# Power.net
KiCad netlist of a schematic drawn in Altium Designer
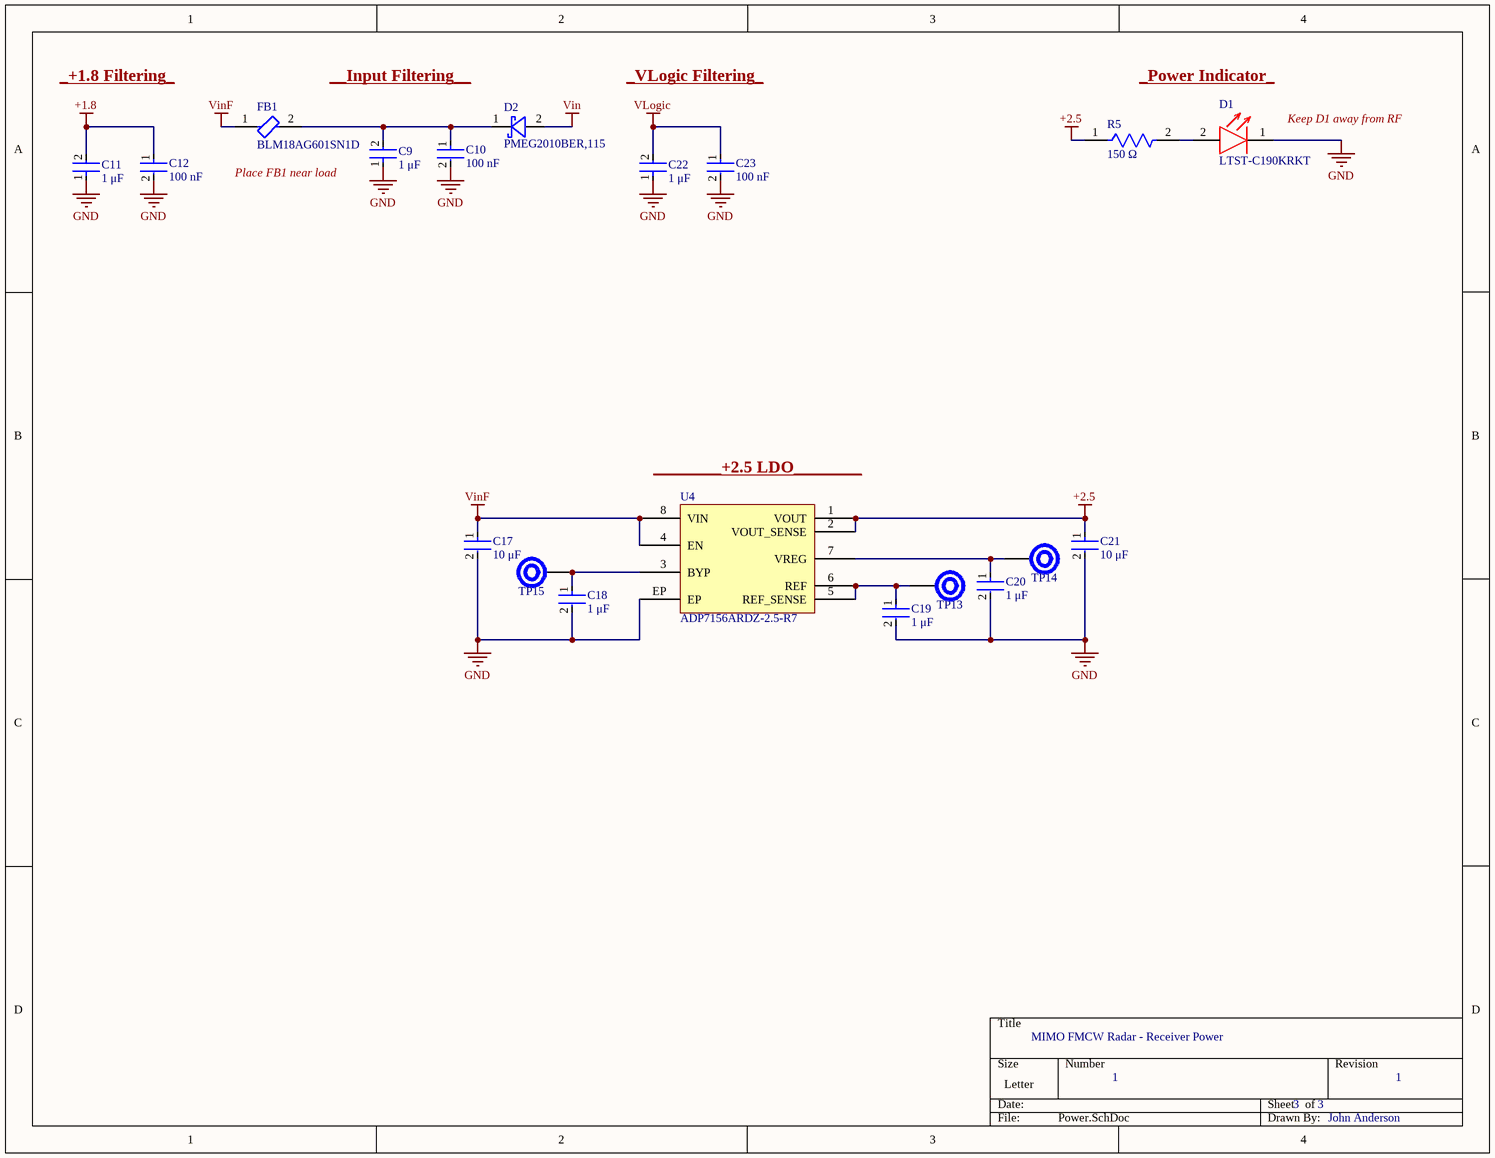
[diagram p0: Power.SchDoc]

(export (version "E")
  (design (tool "Eeschema 10.0.6"))
  (components
    (comp (ref "C9")
      (value "1 μF")
      (footprint "FP-0603-L_1_6_0_15-W_0_8-MFG")
      (libsource (lib "Power Pullers") (part "11868f565c42a9108669ba33697ecf6"))
    )
    (comp (ref "C10")
      (value "100 nF")
      (footprint "FP-CGA3E-0_3-0_1-MFG")
      (libsource (lib "Power Pullers") (part "b4654b650e69147ec39a6b967a45e02"))
    )
    (comp (ref "C11")
      (value "1 μF")
      (footprint "FP-0603-L_1_6_0_15-W_0_8-MFG")
      (libsource (lib "Power Pullers") (part "11868f565c42a9108669ba33697ecf6"))
    )
    (comp (ref "C12")
      (value "100 nF")
      (footprint "FP-CGA3E-0_3-0_1-MFG")
      (libsource (lib "Power Pullers") (part "b4654b650e69147ec39a6b967a45e02"))
    )
    (comp (ref "C17")
      (value "10 μF")
      (footprint "FP-GRM21B-0_15-IPC_C")
      (libsource (lib "Power Pullers") (part "b4654b650e69147ec39a6b967a45e02"))
    )
    (comp (ref "C18")
      (value "1 μF")
      (footprint "FP-0603-L_1_6_0_15-W_0_8-MFG")
      (libsource (lib "Power Pullers") (part "11868f565c42a9108669ba33697ecf6"))
    )
    (comp (ref "C19")
      (value "1 μF")
      (footprint "FP-0603-L_1_6_0_15-W_0_8-MFG")
      (libsource (lib "Power Pullers") (part "11868f565c42a9108669ba33697ecf6"))
    )
    (comp (ref "C20")
      (value "1 μF")
      (footprint "FP-0603-L_1_6_0_15-W_0_8-MFG")
      (libsource (lib "Power Pullers") (part "11868f565c42a9108669ba33697ecf6"))
    )
    (comp (ref "C21")
      (value "10 μF")
      (footprint "FP-GRM21B-0_15-IPC_C")
      (libsource (lib "Power Pullers") (part "b4654b650e69147ec39a6b967a45e02"))
    )
    (comp (ref "C22")
      (value "1 μF")
      (footprint "FP-0603-L_1_6_0_15-W_0_8-MFG")
      (libsource (lib "Power Pullers") (part "11868f565c42a9108669ba33697ecf6"))
    )
    (comp (ref "C23")
      (value "100 nF")
      (footprint "FP-CGA3E-0_3-0_1-MFG")
      (libsource (lib "Power Pullers") (part "b4654b650e69147ec39a6b967a45e02"))
    )
    (comp (ref "D1")
      (value "LTST-C190KRKT")
      (footprint "LTST-C190KRKT-Footprint-1")
      (description "Red, Single Color LED, Red, Water Clear")
      (libsource (lib "Power Pullers") (part "LTST-C190KRKT-Symbol-1"))
    )
    (comp (ref "D2")
      (value "PMEG2010BER,115")
      (footprint "PMEG2010BER,115-Footprint-1")
      (description "PMEG2010 Series 20 V 1 A SMT Low VF MEGA Schottky Barrier Rectifier - SOD-123W")
      (libsource (lib "Power Pullers") (part "PMEG2010BER,115-Symbol-1"))
    )
    (comp (ref "FB1")
      (value "BLM18AG601SN1D")
      (footprint "FP-BLM18-0_15-t0_8-IPC_B")
      (description "Ferrite Beads Multi-Layer 600Ohm 25% 100MHz 500mA 380mOhm DCR 0603 Automotive Paper T/R")
      (fields (field (name "TOLERANCE") "25%"))
      (libsource (lib "Power Pullers") (part "5f30dd21d616792df468990f7003faa"))
    )
    (comp (ref "R5")
      (value "150 Ω")
      (footprint "FP-RMCF0603-IPC_C")
      (description "150 Ohm, Res Thick Film 0603 1% 0.1W ±100ppm/°C Molded SMD Paper T/R")
      (fields (field (name "TOLERANCE") "1%"))
      (libsource (lib "Power Pullers") (part "1029c3af85768c4190bb7ad29bc67b5"))
    )
    (comp (ref "TP13")
      (value "Test Point - 32 mil")
      (footprint "Test Point - 32 mil-Footprint-1")
      (description "32 mil (0.8 mm) test point.")
      (libsource (lib "Power Pullers") (part "Test Point - 32 mil-Symbol-1"))
    )
    (comp (ref "TP14")
      (value "Test Point - 32 mil")
      (footprint "Test Point - 32 mil-Footprint-1")
      (description "32 mil (0.8 mm) test point.")
      (libsource (lib "Power Pullers") (part "Test Point - 32 mil-Symbol-1"))
    )
    (comp (ref "TP15")
      (value "Test Point - 32 mil")
      (footprint "Test Point - 32 mil-Footprint-1")
      (description "32 mil (0.8 mm) test point.")
      (libsource (lib "Power Pullers") (part "Test Point - 32 mil-Symbol-1"))
    )
    (comp (ref "U4")
      (value "ADP7156ARDZ-2.5-R7")
      (footprint "ADP7156ARDZ-2.5-R7-Footprint-1")
      (description "LDO Regulator Pos 2.5V 1.2A 8-Pin SOIC N EP T/R")
      (libsource (lib "Power Pullers") (part "ADP7156ARDZ-2.5-R7-Symbol-1"))
    )
  )
  (nets
    (net (code "1") (name "+1.8") (class "Default")
      (node (ref "C11") (pin "2") (pinfunction "2_2") (pintype "passive"))
      (node (ref "C12") (pin "1") (pinfunction "1_1") (pintype "passive"))
    )
    (net (code "2") (name "+2.5") (class "Default")
      (node (ref "C21") (pin "1") (pinfunction "1_1") (pintype "passive"))
      (node (ref "R5") (pin "1") (pinfunction "1_1") (pintype "passive"))
      (node (ref "U4") (pin "1") (pinfunction "VOUT_1") (pintype "passive"))
      (node (ref "U4") (pin "2") (pinfunction "VOUT_SENSE_2") (pintype "passive"))
    )
    (net (code "3") (name "GND") (class "Default")
      (node (ref "C10") (pin "2") (pinfunction "2_2") (pintype "passive"))
      (node (ref "C11") (pin "1") (pinfunction "1_1") (pintype "passive"))
      (node (ref "C12") (pin "2") (pinfunction "2_2") (pintype "passive"))
      (node (ref "C17") (pin "2") (pinfunction "2_2") (pintype "passive"))
      (node (ref "C18") (pin "2") (pinfunction "2_2") (pintype "passive"))
      (node (ref "C19") (pin "2") (pinfunction "2_2") (pintype "passive"))
      (node (ref "C20") (pin "2") (pinfunction "2_2") (pintype "passive"))
      (node (ref "C21") (pin "2") (pinfunction "2_2") (pintype "passive"))
      (node (ref "C22") (pin "1") (pinfunction "1_1") (pintype "passive"))
      (node (ref "C23") (pin "2") (pinfunction "2_2") (pintype "passive"))
      (node (ref "C9") (pin "1") (pinfunction "1_1") (pintype "passive"))
      (node (ref "D1") (pin "1") (pinfunction "1_1") (pintype "passive"))
      (node (ref "U4") (pin "EP") (pinfunction "EP_EP") (pintype "passive"))
    )
    (net (code "4") (name "Net-(C10-Pad1)") (class "Default")
      (node (ref "C10") (pin "1") (pinfunction "1_1") (pintype "passive"))
      (node (ref "C9") (pin "2") (pinfunction "2_2") (pintype "passive"))
      (node (ref "D2") (pin "1") (pinfunction "1_1") (pintype "passive"))
      (node (ref "FB1") (pin "2") (pinfunction "2_2") (pintype "passive"))
    )
    (net (code "5") (name "Net-(D1-Pad2)") (class "Default")
      (node (ref "D1") (pin "2") (pinfunction "2_2") (pintype "passive"))
      (node (ref "R5") (pin "2") (pinfunction "2_2") (pintype "passive"))
    )
    (net (code "6") (name "Net-(U4-BYP)") (class "Default")
      (node (ref "C18") (pin "1") (pinfunction "1_1") (pintype "passive"))
      (node (ref "TP15") (pin "1") (pinfunction "1_1") (pintype "passive"))
      (node (ref "U4") (pin "3") (pinfunction "BYP_3") (pintype "passive"))
    )
    (net (code "7") (name "Net-(U4-REF)") (class "Default")
      (node (ref "C19") (pin "1") (pinfunction "1_1") (pintype "passive"))
      (node (ref "TP13") (pin "1") (pinfunction "1_1") (pintype "passive"))
      (node (ref "U4") (pin "5") (pinfunction "REF_SENSE_5") (pintype "passive"))
      (node (ref "U4") (pin "6") (pinfunction "REF_6") (pintype "passive"))
    )
    (net (code "8") (name "Net-(U4-VREG)") (class "Default")
      (node (ref "C20") (pin "1") (pinfunction "1_1") (pintype "passive"))
      (node (ref "TP14") (pin "1") (pinfunction "1_1") (pintype "passive"))
      (node (ref "U4") (pin "7") (pinfunction "VREG_7") (pintype "passive"))
    )
    (net (code "9") (name "VLogic") (class "Default")
      (node (ref "C22") (pin "2") (pinfunction "2_2") (pintype "passive"))
      (node (ref "C23") (pin "1") (pinfunction "1_1") (pintype "passive"))
    )
    (net (code "10") (name "Vin") (class "Default")
      (node (ref "D2") (pin "2") (pinfunction "2_2") (pintype "passive"))
    )
    (net (code "11") (name "VinF") (class "Default")
      (node (ref "C17") (pin "1") (pinfunction "1_1") (pintype "passive"))
      (node (ref "FB1") (pin "1") (pinfunction "1_1") (pintype "passive"))
      (node (ref "U4") (pin "4") (pinfunction "EN_4") (pintype "passive"))
      (node (ref "U4") (pin "8") (pinfunction "VIN_8") (pintype "passive"))
    )
  )
)
